# Schematic_L0.net
KiCad netlist of a schematic drawn in Altium Designer
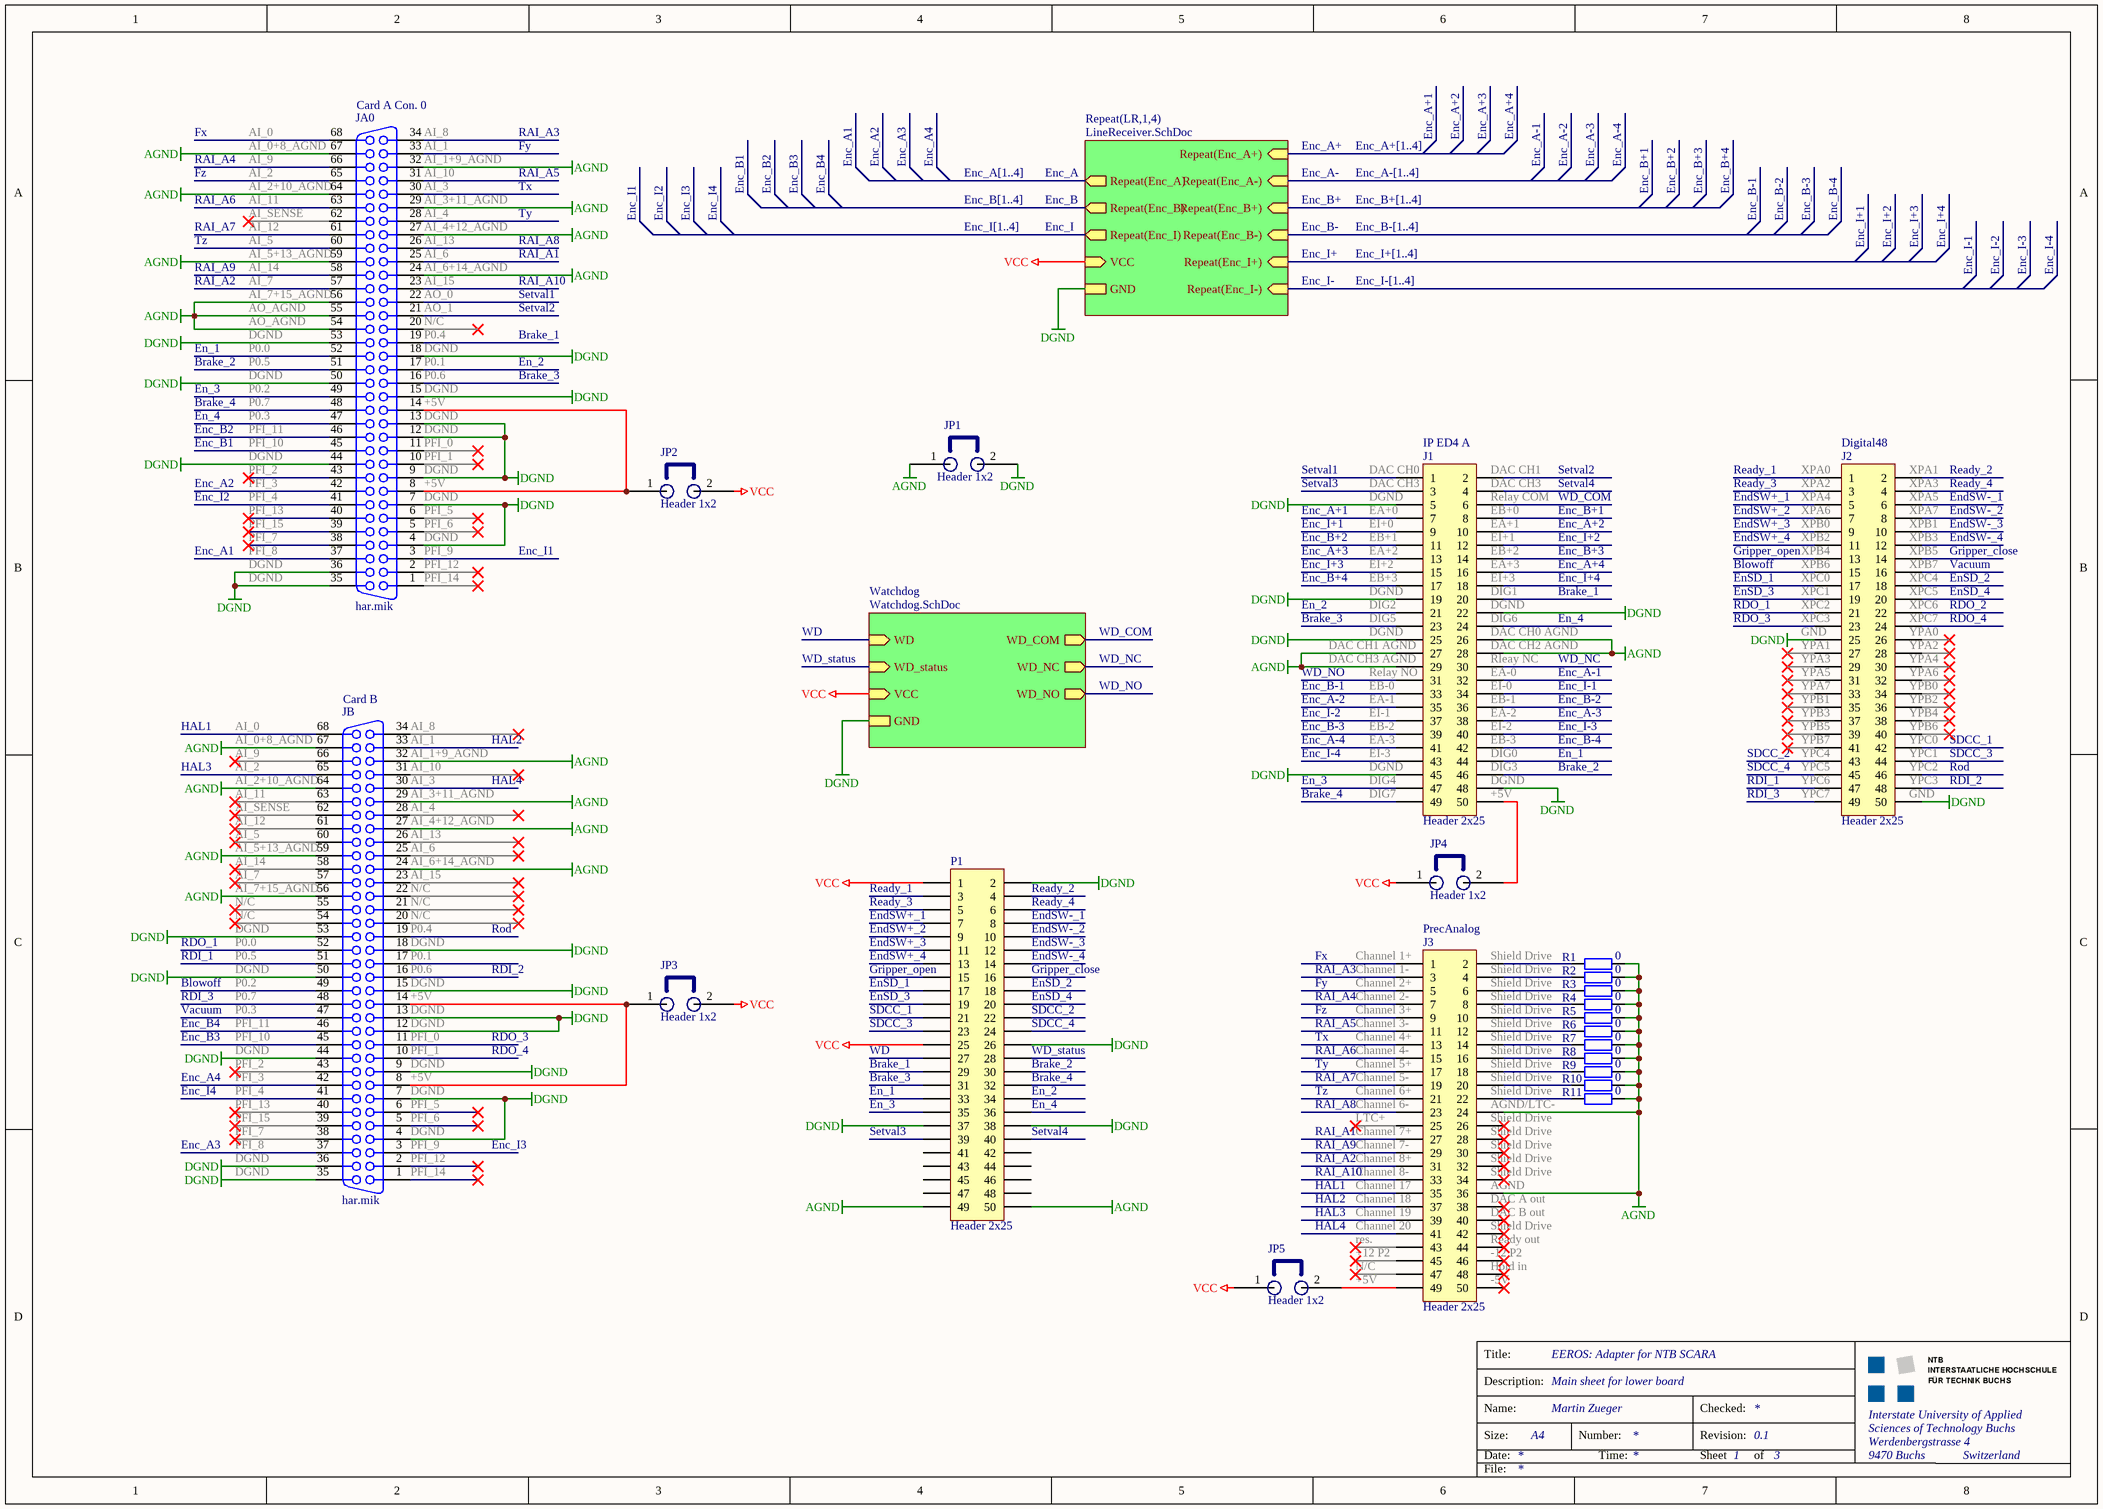
[diagram p0: Schematic_L0.SchDoc]

(export (version "E")
  (design (tool "Eeschema 10.0.6"))
  (components
    (comp (ref "J1")
      (value "Header 2x25")
      (footprint "Header - 2x25 - Boxed")
      (description "Header, 25-Pin, Dual row")
      (fields (field (name "PUBLISHER") "Altium Limited"))
      (libsource (lib "Integrated_Library") (part "Header 2x25"))
    )
    (comp (ref "J2")
      (value "Header 2x25")
      (footprint "Header - 2x25 - Boxed")
      (description "Header, 25-Pin, Dual row")
      (fields (field (name "PUBLISHER") "Altium Limited"))
      (libsource (lib "Integrated_Library") (part "Header 2x25"))
    )
    (comp (ref "J3")
      (value "Header 2x25")
      (footprint "Header - 2x25 - Boxed")
      (description "Header, 25-Pin, Dual row")
      (fields (field (name "PUBLISHER") "Altium Limited"))
      (libsource (lib "Integrated_Library") (part "Header 2x25"))
    )
    (comp (ref "JA0")
      (value "har.mik")
      (footprint "HAR-MIK P/S 68 SA")
      (description "TB 60 01 068 5232")
      (fields (field (name "PUBLISHER") "Altium Limited"))
      (libsource (lib "Integrated_Library") (part "Connector 68"))
    )
    (comp (ref "JB")
      (value "har.mik")
      (footprint "HAR-MIK P/S 68 SA")
      (description "TB 60 01 068 5232")
      (fields (field (name "PUBLISHER") "Altium Limited"))
      (libsource (lib "Integrated_Library") (part "Connector 68"))
    )
    (comp (ref "JP1")
      (value "Header 1x2")
      (footprint "Header - 1x2 - V")
      (libsource (lib "Integrated_Library") (part "Jumper"))
    )
    (comp (ref "JP2")
      (value "Header 1x2")
      (footprint "Header - 1x2 - V")
      (libsource (lib "Integrated_Library") (part "Jumper"))
    )
    (comp (ref "JP3")
      (value "Header 1x2")
      (footprint "Header - 1x2 - V")
      (libsource (lib "Integrated_Library") (part "Jumper"))
    )
    (comp (ref "JP4")
      (value "Header 1x2")
      (footprint "Header - 1x2 - V")
      (libsource (lib "Integrated_Library") (part "Jumper"))
    )
    (comp (ref "JP5")
      (value "Header 1x2")
      (footprint "Header - 1x2 - V")
      (libsource (lib "Integrated_Library") (part "Jumper"))
    )
    (comp (ref "P1")
      (value "Header 2x25")
      (footprint "Header - 2x25 - V")
      (description "Header, 25-Pin, Dual row")
      (fields (field (name "PUBLISHER") "Altium Limited"))
      (libsource (lib "mzueger") (part "Header 2x25"))
    )
    (comp (ref "R1")
      (value "0")
      (footprint "0805")
      (description "Resistor")
      (fields (field (name "#PUBLISHER") "Dr. A. Heinzelmann"))
      (libsource (lib "mzueger") (part "R"))
    )
    (comp (ref "R2")
      (value "0")
      (footprint "0805")
      (description "Resistor")
      (fields (field (name "#PUBLISHER") "Dr. A. Heinzelmann"))
      (libsource (lib "mzueger") (part "R"))
    )
    (comp (ref "R3")
      (value "0")
      (footprint "0805")
      (description "Resistor")
      (fields (field (name "#PUBLISHER") "Dr. A. Heinzelmann"))
      (libsource (lib "mzueger") (part "R"))
    )
    (comp (ref "R4")
      (value "0")
      (footprint "0805")
      (description "Resistor")
      (fields (field (name "#PUBLISHER") "Dr. A. Heinzelmann"))
      (libsource (lib "mzueger") (part "R"))
    )
    (comp (ref "R5")
      (value "0")
      (footprint "0805")
      (description "Resistor")
      (fields (field (name "#PUBLISHER") "Dr. A. Heinzelmann"))
      (libsource (lib "mzueger") (part "R"))
    )
    (comp (ref "R6")
      (value "0")
      (footprint "0805")
      (description "Resistor")
      (fields (field (name "#PUBLISHER") "Dr. A. Heinzelmann"))
      (libsource (lib "mzueger") (part "R"))
    )
    (comp (ref "R7")
      (value "0")
      (footprint "0805")
      (description "Resistor")
      (fields (field (name "#PUBLISHER") "Dr. A. Heinzelmann"))
      (libsource (lib "mzueger") (part "R"))
    )
    (comp (ref "R8")
      (value "0")
      (footprint "0805")
      (description "Resistor")
      (fields (field (name "#PUBLISHER") "Dr. A. Heinzelmann"))
      (libsource (lib "mzueger") (part "R"))
    )
    (comp (ref "R9")
      (value "0")
      (footprint "0805")
      (description "Resistor")
      (fields (field (name "#PUBLISHER") "Dr. A. Heinzelmann"))
      (libsource (lib "mzueger") (part "R"))
    )
    (comp (ref "R10")
      (value "0")
      (footprint "0805")
      (description "Resistor")
      (fields (field (name "#PUBLISHER") "Dr. A. Heinzelmann"))
      (libsource (lib "mzueger") (part "R"))
    )
    (comp (ref "R11")
      (value "0")
      (footprint "0805")
      (description "Resistor")
      (fields (field (name "#PUBLISHER") "Dr. A. Heinzelmann"))
      (libsource (lib "mzueger") (part "R"))
    )
  )
  (nets
    (net (code "1") (name "/Blowoff") (class "Default")
      (node (ref "J2") (pin "15") (pinfunction "15_15") (pintype "passive"))
      (node (ref "JB") (pin "49") (pinfunction "49_49") (pintype "passive"))
    )
    (net (code "2") (name "/Brake_1") (class "Default")
      (node (ref "J1") (pin "20") (pinfunction "20_20") (pintype "passive"))
      (node (ref "JA0") (pin "19") (pinfunction "19_19") (pintype "passive"))
      (node (ref "P1") (pin "29") (pinfunction "29_29") (pintype "passive"))
    )
    (net (code "3") (name "/Brake_2") (class "Default")
      (node (ref "J1") (pin "46") (pinfunction "46_46") (pintype "passive"))
      (node (ref "JA0") (pin "51") (pinfunction "51_51") (pintype "passive"))
      (node (ref "P1") (pin "30") (pinfunction "30_30") (pintype "passive"))
    )
    (net (code "4") (name "/Brake_3") (class "Default")
      (node (ref "J1") (pin "23") (pinfunction "23_23") (pintype "passive"))
      (node (ref "JA0") (pin "16") (pinfunction "16_16") (pintype "passive"))
      (node (ref "P1") (pin "31") (pinfunction "31_31") (pintype "passive"))
    )
    (net (code "5") (name "/Brake_4") (class "Default")
      (node (ref "J1") (pin "49") (pinfunction "49_49") (pintype "passive"))
      (node (ref "JA0") (pin "48") (pinfunction "48_48") (pintype "passive"))
      (node (ref "P1") (pin "32") (pinfunction "32_32") (pintype "passive"))
    )
    (net (code "6") (name "/EnSD_1") (class "Default")
      (node (ref "J2") (pin "17") (pinfunction "17_17") (pintype "passive"))
      (node (ref "P1") (pin "17") (pinfunction "17_17") (pintype "passive"))
    )
    (net (code "7") (name "/EnSD_2") (class "Default")
      (node (ref "J2") (pin "18") (pinfunction "18_18") (pintype "passive"))
      (node (ref "P1") (pin "18") (pinfunction "18_18") (pintype "passive"))
    )
    (net (code "8") (name "/EnSD_3") (class "Default")
      (node (ref "J2") (pin "19") (pinfunction "19_19") (pintype "passive"))
      (node (ref "P1") (pin "19") (pinfunction "19_19") (pintype "passive"))
    )
    (net (code "9") (name "/EnSD_4") (class "Default")
      (node (ref "J2") (pin "20") (pinfunction "20_20") (pintype "passive"))
      (node (ref "P1") (pin "20") (pinfunction "20_20") (pintype "passive"))
    )
    (net (code "10") (name "/En_1") (class "Default")
      (node (ref "J1") (pin "44") (pinfunction "44_44") (pintype "passive"))
      (node (ref "JA0") (pin "52") (pinfunction "52_52") (pintype "passive"))
      (node (ref "P1") (pin "33") (pinfunction "33_33") (pintype "passive"))
    )
    (net (code "11") (name "/En_2") (class "Default")
      (node (ref "J1") (pin "21") (pinfunction "21_21") (pintype "passive"))
      (node (ref "JA0") (pin "17") (pinfunction "17_17") (pintype "passive"))
      (node (ref "P1") (pin "34") (pinfunction "34_34") (pintype "passive"))
    )
    (net (code "12") (name "/En_3") (class "Default")
      (node (ref "J1") (pin "47") (pinfunction "47_47") (pintype "passive"))
      (node (ref "JA0") (pin "49") (pinfunction "49_49") (pintype "passive"))
      (node (ref "P1") (pin "35") (pinfunction "35_35") (pintype "passive"))
    )
    (net (code "13") (name "/En_4") (class "Default")
      (node (ref "J1") (pin "24") (pinfunction "24_24") (pintype "passive"))
      (node (ref "JA0") (pin "47") (pinfunction "47_47") (pintype "passive"))
      (node (ref "P1") (pin "36") (pinfunction "36_36") (pintype "passive"))
    )
    (net (code "16") (name "/Enc_A+1") (class "Default")
      (node (ref "J1") (pin "7") (pinfunction "7_7") (pintype "passive"))
    )
    (net (code "17") (name "/Enc_A+2") (class "Default")
      (node (ref "J1") (pin "10") (pinfunction "10_10") (pintype "passive"))
    )
    (net (code "18") (name "/Enc_A+3") (class "Default")
      (node (ref "J1") (pin "13") (pinfunction "13_13") (pintype "passive"))
    )
    (net (code "19") (name "/Enc_A+4") (class "Default")
      (node (ref "J1") (pin "16") (pinfunction "16_16") (pintype "passive"))
    )
    (net (code "22") (name "/Enc_A-1") (class "Default")
      (node (ref "J1") (pin "32") (pinfunction "32_32") (pintype "passive"))
    )
    (net (code "23") (name "/Enc_A-2") (class "Default")
      (node (ref "J1") (pin "35") (pinfunction "35_35") (pintype "passive"))
    )
    (net (code "24") (name "/Enc_A-3") (class "Default")
      (node (ref "J1") (pin "38") (pinfunction "38_38") (pintype "passive"))
    )
    (net (code "25") (name "/Enc_A-4") (class "Default")
      (node (ref "J1") (pin "41") (pinfunction "41_41") (pintype "passive"))
    )
    (net (code "27") (name "/Enc_A1") (class "Default")
      (node (ref "JA0") (pin "37") (pinfunction "37_37") (pintype "passive"))
    )
    (net (code "28") (name "/Enc_A2") (class "Default")
      (node (ref "JA0") (pin "42") (pinfunction "42_42") (pintype "passive"))
    )
    (net (code "29") (name "/Enc_A3") (class "Default")
      (node (ref "JB") (pin "37") (pinfunction "37_37") (pintype "passive"))
    )
    (net (code "30") (name "/Enc_A4") (class "Default")
      (node (ref "JB") (pin "42") (pinfunction "42_42") (pintype "passive"))
    )
    (net (code "34") (name "/Enc_B+1") (class "Default")
      (node (ref "J1") (pin "8") (pinfunction "8_8") (pintype "passive"))
    )
    (net (code "35") (name "/Enc_B+2") (class "Default")
      (node (ref "J1") (pin "11") (pinfunction "11_11") (pintype "passive"))
    )
    (net (code "36") (name "/Enc_B+3") (class "Default")
      (node (ref "J1") (pin "14") (pinfunction "14_14") (pintype "passive"))
    )
    (net (code "37") (name "/Enc_B+4") (class "Default")
      (node (ref "J1") (pin "17") (pinfunction "17_17") (pintype "passive"))
    )
    (net (code "40") (name "/Enc_B-1") (class "Default")
      (node (ref "J1") (pin "33") (pinfunction "33_33") (pintype "passive"))
    )
    (net (code "41") (name "/Enc_B-2") (class "Default")
      (node (ref "J1") (pin "36") (pinfunction "36_36") (pintype "passive"))
    )
    (net (code "42") (name "/Enc_B-3") (class "Default")
      (node (ref "J1") (pin "39") (pinfunction "39_39") (pintype "passive"))
    )
    (net (code "43") (name "/Enc_B-4") (class "Default")
      (node (ref "J1") (pin "42") (pinfunction "42_42") (pintype "passive"))
    )
    (net (code "45") (name "/Enc_B1") (class "Default")
      (node (ref "JA0") (pin "45") (pinfunction "45_45") (pintype "passive"))
    )
    (net (code "46") (name "/Enc_B2") (class "Default")
      (node (ref "JA0") (pin "46") (pinfunction "46_46") (pintype "passive"))
    )
    (net (code "47") (name "/Enc_B3") (class "Default")
      (node (ref "JB") (pin "45") (pinfunction "45_45") (pintype "passive"))
    )
    (net (code "48") (name "/Enc_B4") (class "Default")
      (node (ref "JB") (pin "46") (pinfunction "46_46") (pintype "passive"))
    )
    (net (code "52") (name "/Enc_I+1") (class "Default")
      (node (ref "J1") (pin "9") (pinfunction "9_9") (pintype "passive"))
    )
    (net (code "53") (name "/Enc_I+2") (class "Default")
      (node (ref "J1") (pin "12") (pinfunction "12_12") (pintype "passive"))
    )
    (net (code "54") (name "/Enc_I+3") (class "Default")
      (node (ref "J1") (pin "15") (pinfunction "15_15") (pintype "passive"))
    )
    (net (code "55") (name "/Enc_I+4") (class "Default")
      (node (ref "J1") (pin "18") (pinfunction "18_18") (pintype "passive"))
    )
    (net (code "58") (name "/Enc_I-1") (class "Default")
      (node (ref "J1") (pin "34") (pinfunction "34_34") (pintype "passive"))
    )
    (net (code "59") (name "/Enc_I-2") (class "Default")
      (node (ref "J1") (pin "37") (pinfunction "37_37") (pintype "passive"))
    )
    (net (code "60") (name "/Enc_I-3") (class "Default")
      (node (ref "J1") (pin "40") (pinfunction "40_40") (pintype "passive"))
    )
    (net (code "61") (name "/Enc_I-4") (class "Default")
      (node (ref "J1") (pin "43") (pinfunction "43_43") (pintype "passive"))
    )
    (net (code "63") (name "/Enc_I1") (class "Default")
      (node (ref "JA0") (pin "3") (pinfunction "3_3") (pintype "passive"))
    )
    (net (code "64") (name "/Enc_I2") (class "Default")
      (node (ref "JA0") (pin "41") (pinfunction "41_41") (pintype "passive"))
    )
    (net (code "65") (name "/Enc_I3") (class "Default")
      (node (ref "JB") (pin "3") (pinfunction "3_3") (pintype "passive"))
    )
    (net (code "66") (name "/Enc_I4") (class "Default")
      (node (ref "JB") (pin "41") (pinfunction "41_41") (pintype "passive"))
    )
    (net (code "68") (name "/EndSW+_1") (class "Default")
      (node (ref "J2") (pin "5") (pinfunction "5_5") (pintype "passive"))
      (node (ref "P1") (pin "7") (pinfunction "7_7") (pintype "passive"))
    )
    (net (code "69") (name "/EndSW+_2") (class "Default")
      (node (ref "J2") (pin "7") (pinfunction "7_7") (pintype "passive"))
      (node (ref "P1") (pin "9") (pinfunction "9_9") (pintype "passive"))
    )
    (net (code "70") (name "/EndSW+_3") (class "Default")
      (node (ref "J2") (pin "9") (pinfunction "9_9") (pintype "passive"))
      (node (ref "P1") (pin "11") (pinfunction "11_11") (pintype "passive"))
    )
    (net (code "71") (name "/EndSW+_4") (class "Default")
      (node (ref "J2") (pin "11") (pinfunction "11_11") (pintype "passive"))
      (node (ref "P1") (pin "13") (pinfunction "13_13") (pintype "passive"))
    )
    (net (code "72") (name "/EndSW-_1") (class "Default")
      (node (ref "J2") (pin "6") (pinfunction "6_6") (pintype "passive"))
      (node (ref "P1") (pin "8") (pinfunction "8_8") (pintype "passive"))
    )
    (net (code "73") (name "/EndSW-_2") (class "Default")
      (node (ref "J2") (pin "8") (pinfunction "8_8") (pintype "passive"))
      (node (ref "P1") (pin "10") (pinfunction "10_10") (pintype "passive"))
    )
    (net (code "74") (name "/EndSW-_3") (class "Default")
      (node (ref "J2") (pin "10") (pinfunction "10_10") (pintype "passive"))
      (node (ref "P1") (pin "12") (pinfunction "12_12") (pintype "passive"))
    )
    (net (code "75") (name "/EndSW-_4") (class "Default")
      (node (ref "J2") (pin "12") (pinfunction "12_12") (pintype "passive"))
      (node (ref "P1") (pin "14") (pinfunction "14_14") (pintype "passive"))
    )
    (net (code "76") (name "/Fx") (class "Default")
      (node (ref "J3") (pin "1") (pinfunction "1_1") (pintype "passive"))
      (node (ref "JA0") (pin "68") (pinfunction "68_68") (pintype "passive"))
    )
    (net (code "77") (name "/Fy") (class "Default")
      (node (ref "J3") (pin "5") (pinfunction "5_5") (pintype "passive"))
      (node (ref "JA0") (pin "33") (pinfunction "33_33") (pintype "passive"))
    )
    (net (code "78") (name "/Fz") (class "Default")
      (node (ref "J3") (pin "9") (pinfunction "9_9") (pintype "passive"))
      (node (ref "JA0") (pin "65") (pinfunction "65_65") (pintype "passive"))
    )
    (net (code "79") (name "/Gripper_close") (class "Default")
      (node (ref "J2") (pin "14") (pinfunction "14_14") (pintype "passive"))
      (node (ref "P1") (pin "16") (pinfunction "16_16") (pintype "passive"))
    )
    (net (code "80") (name "/Gripper_open") (class "Default")
      (node (ref "J2") (pin "13") (pinfunction "13_13") (pintype "passive"))
      (node (ref "P1") (pin "15") (pinfunction "15_15") (pintype "passive"))
    )
    (net (code "81") (name "/HAL1") (class "Default")
      (node (ref "J3") (pin "35") (pinfunction "35_35") (pintype "passive"))
      (node (ref "JB") (pin "68") (pinfunction "68_68") (pintype "passive"))
    )
    (net (code "82") (name "/HAL2") (class "Default")
      (node (ref "J3") (pin "37") (pinfunction "37_37") (pintype "passive"))
      (node (ref "JB") (pin "33") (pinfunction "33_33") (pintype "passive"))
    )
    (net (code "83") (name "/HAL3") (class "Default")
      (node (ref "J3") (pin "39") (pinfunction "39_39") (pintype "passive"))
      (node (ref "JB") (pin "65") (pinfunction "65_65") (pintype "passive"))
    )
    (net (code "84") (name "/HAL4") (class "Default")
      (node (ref "J3") (pin "41") (pinfunction "41_41") (pintype "passive"))
      (node (ref "JB") (pin "30") (pinfunction "30_30") (pintype "passive"))
    )
    (net (code "85") (name "/RAI_A1") (class "Default")
      (node (ref "J3") (pin "27") (pinfunction "27_27") (pintype "passive"))
      (node (ref "JA0") (pin "25") (pinfunction "25_25") (pintype "passive"))
    )
    (net (code "86") (name "/RAI_A2") (class "Default")
      (node (ref "J3") (pin "31") (pinfunction "31_31") (pintype "passive"))
      (node (ref "JA0") (pin "57") (pinfunction "57_57") (pintype "passive"))
    )
    (net (code "87") (name "/RAI_A3") (class "Default")
      (node (ref "J3") (pin "3") (pinfunction "3_3") (pintype "passive"))
      (node (ref "JA0") (pin "34") (pinfunction "34_34") (pintype "passive"))
    )
    (net (code "88") (name "/RAI_A4") (class "Default")
      (node (ref "J3") (pin "7") (pinfunction "7_7") (pintype "passive"))
      (node (ref "JA0") (pin "66") (pinfunction "66_66") (pintype "passive"))
    )
    (net (code "89") (name "/RAI_A5") (class "Default")
      (node (ref "J3") (pin "11") (pinfunction "11_11") (pintype "passive"))
      (node (ref "JA0") (pin "31") (pinfunction "31_31") (pintype "passive"))
    )
    (net (code "90") (name "/RAI_A6") (class "Default")
      (node (ref "J3") (pin "15") (pinfunction "15_15") (pintype "passive"))
      (node (ref "JA0") (pin "63") (pinfunction "63_63") (pintype "passive"))
    )
    (net (code "91") (name "/RAI_A7") (class "Default")
      (node (ref "J3") (pin "19") (pinfunction "19_19") (pintype "passive"))
      (node (ref "JA0") (pin "61") (pinfunction "61_61") (pintype "passive"))
    )
    (net (code "92") (name "/RAI_A8") (class "Default")
      (node (ref "J3") (pin "23") (pinfunction "23_23") (pintype "passive"))
      (node (ref "JA0") (pin "26") (pinfunction "26_26") (pintype "passive"))
    )
    (net (code "93") (name "/RAI_A9") (class "Default")
      (node (ref "J3") (pin "29") (pinfunction "29_29") (pintype "passive"))
      (node (ref "JA0") (pin "58") (pinfunction "58_58") (pintype "passive"))
    )
    (net (code "94") (name "/RAI_A10") (class "Default")
      (node (ref "J3") (pin "33") (pinfunction "33_33") (pintype "passive"))
      (node (ref "JA0") (pin "23") (pinfunction "23_23") (pintype "passive"))
    )
    (net (code "95") (name "/RDI_1") (class "Default")
      (node (ref "J2") (pin "47") (pinfunction "47_47") (pintype "passive"))
      (node (ref "JB") (pin "51") (pinfunction "51_51") (pintype "passive"))
    )
    (net (code "96") (name "/RDI_2") (class "Default")
      (node (ref "J2") (pin "48") (pinfunction "48_48") (pintype "passive"))
      (node (ref "JB") (pin "16") (pinfunction "16_16") (pintype "passive"))
    )
    (net (code "97") (name "/RDI_3") (class "Default")
      (node (ref "J2") (pin "49") (pinfunction "49_49") (pintype "passive"))
      (node (ref "JB") (pin "48") (pinfunction "48_48") (pintype "passive"))
    )
    (net (code "98") (name "/RDO_1") (class "Default")
      (node (ref "J2") (pin "21") (pinfunction "21_21") (pintype "passive"))
      (node (ref "JB") (pin "52") (pinfunction "52_52") (pintype "passive"))
    )
    (net (code "99") (name "/RDO_2") (class "Default")
      (node (ref "J2") (pin "22") (pinfunction "22_22") (pintype "passive"))
    )
    (net (code "100") (name "/RDO_3") (class "Default")
      (node (ref "J2") (pin "23") (pinfunction "23_23") (pintype "passive"))
      (node (ref "JB") (pin "11") (pinfunction "11_11") (pintype "passive"))
    )
    (net (code "101") (name "/RDO_4") (class "Default")
      (node (ref "J2") (pin "24") (pinfunction "24_24") (pintype "passive"))
      (node (ref "JB") (pin "10") (pinfunction "10_10") (pintype "passive"))
    )
    (net (code "102") (name "/Ready_1") (class "Default")
      (node (ref "J2") (pin "1") (pinfunction "1_1") (pintype "passive"))
      (node (ref "P1") (pin "3") (pinfunction "3_3") (pintype "passive"))
    )
    (net (code "103") (name "/Ready_2") (class "Default")
      (node (ref "J2") (pin "2") (pinfunction "2_2") (pintype "passive"))
      (node (ref "P1") (pin "4") (pinfunction "4_4") (pintype "passive"))
    )
    (net (code "104") (name "/Ready_3") (class "Default")
      (node (ref "J2") (pin "3") (pinfunction "3_3") (pintype "passive"))
      (node (ref "P1") (pin "5") (pinfunction "5_5") (pintype "passive"))
    )
    (net (code "105") (name "/Ready_4") (class "Default")
      (node (ref "J2") (pin "4") (pinfunction "4_4") (pintype "passive"))
      (node (ref "P1") (pin "6") (pinfunction "6_6") (pintype "passive"))
    )
    (net (code "106") (name "/Rod") (class "Default")
      (node (ref "J2") (pin "46") (pinfunction "46_46") (pintype "passive"))
      (node (ref "JB") (pin "19") (pinfunction "19_19") (pintype "passive"))
    )
    (net (code "107") (name "/SDCC_1") (class "Default")
      (node (ref "J2") (pin "42") (pinfunction "42_42") (pintype "passive"))
      (node (ref "P1") (pin "21") (pinfunction "21_21") (pintype "passive"))
    )
    (net (code "108") (name "/SDCC_2") (class "Default")
      (node (ref "J2") (pin "43") (pinfunction "43_43") (pintype "passive"))
      (node (ref "P1") (pin "22") (pinfunction "22_22") (pintype "passive"))
    )
    (net (code "109") (name "/SDCC_3") (class "Default")
      (node (ref "J2") (pin "44") (pinfunction "44_44") (pintype "passive"))
      (node (ref "P1") (pin "23") (pinfunction "23_23") (pintype "passive"))
    )
    (net (code "110") (name "/SDCC_4") (class "Default")
      (node (ref "J2") (pin "45") (pinfunction "45_45") (pintype "passive"))
      (node (ref "P1") (pin "24") (pinfunction "24_24") (pintype "passive"))
    )
    (net (code "111") (name "/Setval1") (class "Default")
      (node (ref "J1") (pin "1") (pinfunction "1_1") (pintype "passive"))
      (node (ref "JA0") (pin "22") (pinfunction "22_22") (pintype "passive"))
    )
    (net (code "112") (name "/Setval2") (class "Default")
      (node (ref "J1") (pin "2") (pinfunction "2_2") (pintype "passive"))
      (node (ref "JA0") (pin "21") (pinfunction "21_21") (pintype "passive"))
    )
    (net (code "113") (name "/Setval3") (class "Default")
      (node (ref "J1") (pin "3") (pinfunction "3_3") (pintype "passive"))
      (node (ref "P1") (pin "39") (pinfunction "39_39") (pintype "passive"))
    )
    (net (code "114") (name "/Setval4") (class "Default")
      (node (ref "J1") (pin "4") (pinfunction "4_4") (pintype "passive"))
      (node (ref "P1") (pin "40") (pinfunction "40_40") (pintype "passive"))
    )
    (net (code "115") (name "/Tx") (class "Default")
      (node (ref "J3") (pin "13") (pinfunction "13_13") (pintype "passive"))
      (node (ref "JA0") (pin "30") (pinfunction "30_30") (pintype "passive"))
    )
    (net (code "116") (name "/Ty") (class "Default")
      (node (ref "J3") (pin "17") (pinfunction "17_17") (pintype "passive"))
      (node (ref "JA0") (pin "28") (pinfunction "28_28") (pintype "passive"))
    )
    (net (code "117") (name "/Tz") (class "Default")
      (node (ref "J3") (pin "21") (pinfunction "21_21") (pintype "passive"))
      (node (ref "JA0") (pin "60") (pinfunction "60_60") (pintype "passive"))
    )
    (net (code "118") (name "/Vacuum") (class "Default")
      (node (ref "J2") (pin "16") (pinfunction "16_16") (pintype "passive"))
      (node (ref "JB") (pin "47") (pinfunction "47_47") (pintype "passive"))
    )
    (net (code "119") (name "/WD") (class "Default")
      (node (ref "P1") (pin "27") (pinfunction "27_27") (pintype "passive"))
    )
    (net (code "120") (name "/WD_COM") (class "Default")
      (node (ref "J1") (pin "6") (pinfunction "6_6") (pintype "passive"))
    )
    (net (code "121") (name "/WD_NC") (class "Default")
      (node (ref "J1") (pin "30") (pinfunction "30_30") (pintype "passive"))
    )
    (net (code "122") (name "/WD_NO") (class "Default")
      (node (ref "J1") (pin "31") (pinfunction "31_31") (pintype "passive"))
    )
    (net (code "123") (name "/WD_status") (class "Default")
      (node (ref "P1") (pin "28") (pinfunction "28_28") (pintype "passive"))
    )
    (net (code "124") (name "AGND") (class "Default")
      (node (ref "J1") (pin "26") (pinfunction "26_26") (pintype "passive"))
      (node (ref "J1") (pin "27") (pinfunction "27_27") (pintype "passive"))
      (node (ref "J1") (pin "28") (pinfunction "28_28") (pintype "passive"))
      (node (ref "J1") (pin "29") (pinfunction "29_29") (pintype "passive"))
      (node (ref "J3") (pin "24") (pinfunction "24_24") (pintype "passive"))
      (node (ref "J3") (pin "36") (pinfunction "36_36") (pintype "passive"))
      (node (ref "JA0") (pin "24") (pinfunction "24_24") (pintype "passive"))
      (node (ref "JA0") (pin "27") (pinfunction "27_27") (pintype "passive"))
      (node (ref "JA0") (pin "29") (pinfunction "29_29") (pintype "passive"))
      (node (ref "JA0") (pin "32") (pinfunction "32_32") (pintype "passive"))
      (node (ref "JA0") (pin "54") (pinfunction "54_54") (pintype "passive"))
      (node (ref "JA0") (pin "55") (pinfunction "55_55") (pintype "passive"))
      (node (ref "JA0") (pin "56") (pinfunction "56_56") (pintype "passive"))
      (node (ref "JA0") (pin "59") (pinfunction "59_59") (pintype "passive"))
      (node (ref "JA0") (pin "64") (pinfunction "64_64") (pintype "passive"))
      (node (ref "JA0") (pin "67") (pinfunction "67_67") (pintype "passive"))
      (node (ref "JB") (pin "24") (pinfunction "24_24") (pintype "passive"))
      (node (ref "JB") (pin "27") (pinfunction "27_27") (pintype "passive"))
      (node (ref "JB") (pin "29") (pinfunction "29_29") (pintype "passive"))
      (node (ref "JB") (pin "32") (pinfunction "32_32") (pintype "passive"))
      (node (ref "JB") (pin "56") (pinfunction "56_56") (pintype "passive"))
      (node (ref "JB") (pin "59") (pinfunction "59_59") (pintype "passive"))
      (node (ref "JB") (pin "64") (pinfunction "64_64") (pintype "passive"))
      (node (ref "JB") (pin "67") (pinfunction "67_67") (pintype "passive"))
      (node (ref "JP1") (pin "1") (pinfunction "1_1") (pintype "passive"))
      (node (ref "P1") (pin "49") (pinfunction "49_49") (pintype "passive"))
      (node (ref "P1") (pin "50") (pinfunction "50_50") (pintype "passive"))
      (node (ref "R1") (pin "2") (pinfunction "2_2") (pintype "passive"))
      (node (ref "R10") (pin "2") (pinfunction "2_2") (pintype "passive"))
      (node (ref "R11") (pin "2") (pinfunction "2_2") (pintype "passive"))
      (node (ref "R2") (pin "2") (pinfunction "2_2") (pintype "passive"))
      (node (ref "R3") (pin "2") (pinfunction "2_2") (pintype "passive"))
      (node (ref "R4") (pin "2") (pinfunction "2_2") (pintype "passive"))
      (node (ref "R5") (pin "2") (pinfunction "2_2") (pintype "passive"))
      (node (ref "R6") (pin "2") (pinfunction "2_2") (pintype "passive"))
      (node (ref "R7") (pin "2") (pinfunction "2_2") (pintype "passive"))
      (node (ref "R8") (pin "2") (pinfunction "2_2") (pintype "passive"))
      (node (ref "R9") (pin "2") (pinfunction "2_2") (pintype "passive"))
    )
    (net (code "125") (name "DGND") (class "Default")
      (node (ref "J1") (pin "19") (pinfunction "19_19") (pintype "passive"))
      (node (ref "J1") (pin "22") (pinfunction "22_22") (pintype "passive"))
      (node (ref "J1") (pin "25") (pinfunction "25_25") (pintype "passive"))
      (node (ref "J1") (pin "45") (pinfunction "45_45") (pintype "passive"))
      (node (ref "J1") (pin "48") (pinfunction "48_48") (pintype "passive"))
      (node (ref "J1") (pin "5") (pinfunction "5_5") (pintype "passive"))
      (node (ref "J2") (pin "25") (pinfunction "25_25") (pintype "passive"))
      (node (ref "J2") (pin "50") (pinfunction "50_50") (pintype "passive"))
      (node (ref "JA0") (pin "12") (pinfunction "12_12") (pintype "passive"))
      (node (ref "JA0") (pin "13") (pinfunction "13_13") (pintype "passive"))
      (node (ref "JA0") (pin "15") (pinfunction "15_15") (pintype "passive"))
      (node (ref "JA0") (pin "18") (pinfunction "18_18") (pintype "passive"))
      (node (ref "JA0") (pin "35") (pinfunction "35_35") (pintype "passive"))
      (node (ref "JA0") (pin "36") (pinfunction "36_36") (pintype "passive"))
      (node (ref "JA0") (pin "4") (pinfunction "4_4") (pintype "passive"))
      (node (ref "JA0") (pin "44") (pinfunction "44_44") (pintype "passive"))
      (node (ref "JA0") (pin "50") (pinfunction "50_50") (pintype "passive"))
      (node (ref "JA0") (pin "53") (pinfunction "53_53") (pintype "passive"))
      (node (ref "JA0") (pin "7") (pinfunction "7_7") (pintype "passive"))
      (node (ref "JA0") (pin "9") (pinfunction "9_9") (pintype "passive"))
      (node (ref "JB") (pin "12") (pinfunction "12_12") (pintype "passive"))
      (node (ref "JB") (pin "13") (pinfunction "13_13") (pintype "passive"))
      (node (ref "JB") (pin "15") (pinfunction "15_15") (pintype "passive"))
      (node (ref "JB") (pin "18") (pinfunction "18_18") (pintype "passive"))
      (node (ref "JB") (pin "35") (pinfunction "35_35") (pintype "passive"))
      (node (ref "JB") (pin "36") (pinfunction "36_36") (pintype "passive"))
      (node (ref "JB") (pin "4") (pinfunction "4_4") (pintype "passive"))
      (node (ref "JB") (pin "44") (pinfunction "44_44") (pintype "passive"))
      (node (ref "JB") (pin "50") (pinfunction "50_50") (pintype "passive"))
      (node (ref "JB") (pin "53") (pinfunction "53_53") (pintype "passive"))
      (node (ref "JB") (pin "7") (pinfunction "7_7") (pintype "passive"))
      (node (ref "JB") (pin "9") (pinfunction "9_9") (pintype "passive"))
      (node (ref "JP1") (pin "2") (pinfunction "2_2") (pintype "passive"))
      (node (ref "P1") (pin "2") (pinfunction "2_2") (pintype "passive"))
      (node (ref "P1") (pin "26") (pinfunction "26_26") (pintype "passive"))
      (node (ref "P1") (pin "37") (pinfunction "37_37") (pintype "passive"))
      (node (ref "P1") (pin "38") (pinfunction "38_38") (pintype "passive"))
    )
    (net (code "126") (name "Net-(J1-Pad50)") (class "Default")
      (node (ref "J1") (pin "50") (pinfunction "50_50") (pintype "passive"))
      (node (ref "JP4") (pin "2") (pinfunction "2_2") (pintype "passive"))
    )
    (net (code "127") (name "Net-(J3-Pad2)") (class "Default")
      (node (ref "J3") (pin "2") (pinfunction "2_2") (pintype "passive"))
      (node (ref "R1") (pin "1") (pinfunction "1_1") (pintype "passive"))
    )
    (net (code "128") (name "Net-(J3-Pad4)") (class "Default")
      (node (ref "J3") (pin "4") (pinfunction "4_4") (pintype "passive"))
      (node (ref "R2") (pin "1") (pinfunction "1_1") (pintype "passive"))
    )
    (net (code "129") (name "Net-(J3-Pad6)") (class "Default")
      (node (ref "J3") (pin "6") (pinfunction "6_6") (pintype "passive"))
      (node (ref "R3") (pin "1") (pinfunction "1_1") (pintype "passive"))
    )
    (net (code "130") (name "Net-(J3-Pad8)") (class "Default")
      (node (ref "J3") (pin "8") (pinfunction "8_8") (pintype "passive"))
      (node (ref "R4") (pin "1") (pinfunction "1_1") (pintype "passive"))
    )
    (net (code "131") (name "Net-(J3-Pad10)") (class "Default")
      (node (ref "J3") (pin "10") (pinfunction "10_10") (pintype "passive"))
      (node (ref "R5") (pin "1") (pinfunction "1_1") (pintype "passive"))
    )
    (net (code "132") (name "Net-(J3-Pad12)") (class "Default")
      (node (ref "J3") (pin "12") (pinfunction "12_12") (pintype "passive"))
      (node (ref "R6") (pin "1") (pinfunction "1_1") (pintype "passive"))
    )
    (net (code "133") (name "Net-(J3-Pad14)") (class "Default")
      (node (ref "J3") (pin "14") (pinfunction "14_14") (pintype "passive"))
      (node (ref "R7") (pin "1") (pinfunction "1_1") (pintype "passive"))
    )
    (net (code "134") (name "Net-(J3-Pad16)") (class "Default")
      (node (ref "J3") (pin "16") (pinfunction "16_16") (pintype "passive"))
      (node (ref "R8") (pin "1") (pinfunction "1_1") (pintype "passive"))
    )
    (net (code "135") (name "Net-(J3-Pad18)") (class "Default")
      (node (ref "J3") (pin "18") (pinfunction "18_18") (pintype "passive"))
      (node (ref "R9") (pin "1") (pinfunction "1_1") (pintype "passive"))
    )
    (net (code "136") (name "Net-(J3-Pad20)") (class "Default")
      (node (ref "J3") (pin "20") (pinfunction "20_20") (pintype "passive"))
      (node (ref "R10") (pin "1") (pinfunction "1_1") (pintype "passive"))
    )
    (net (code "137") (name "Net-(J3-Pad22)") (class "Default")
      (node (ref "J3") (pin "22") (pinfunction "22_22") (pintype "passive"))
      (node (ref "R11") (pin "1") (pinfunction "1_1") (pintype "passive"))
    )
    (net (code "138") (name "Net-(J3-Pad49)") (class "Default")
      (node (ref "J3") (pin "49") (pinfunction "49_49") (pintype "passive"))
      (node (ref "JP5") (pin "2") (pinfunction "2_2") (pintype "passive"))
    )
    (net (code "139") (name "Net-(JA0-Pad14)") (class "Default")
      (node (ref "JA0") (pin "14") (pinfunction "14_14") (pintype "passive"))
      (node (ref "JA0") (pin "8") (pinfunction "8_8") (pintype "passive"))
      (node (ref "JP2") (pin "1") (pinfunction "1_1") (pintype "passive"))
    )
    (net (code "140") (name "Net-(JB-Pad14)") (class "Default")
      (node (ref "JB") (pin "14") (pinfunction "14_14") (pintype "passive"))
      (node (ref "JB") (pin "8") (pinfunction "8_8") (pintype "passive"))
      (node (ref "JP3") (pin "1") (pinfunction "1_1") (pintype "passive"))
    )
    (net (code "141") (name "VCC") (class "Default")
      (node (ref "JP2") (pin "2") (pinfunction "2_2") (pintype "passive"))
      (node (ref "JP3") (pin "2") (pinfunction "2_2") (pintype "passive"))
      (node (ref "JP4") (pin "1") (pinfunction "1_1") (pintype "passive"))
      (node (ref "JP5") (pin "1") (pinfunction "1_1") (pintype "passive"))
      (node (ref "P1") (pin "1") (pinfunction "1_1") (pintype "passive"))
      (node (ref "P1") (pin "25") (pinfunction "25_25") (pintype "passive"))
    )
    (net (code "142") (name "unconnected-(J2-Pad26)") (class "Default")
      (node (ref "J2") (pin "26") (pinfunction "26_26") (pintype "passive+no_connect"))
    )
    (net (code "143") (name "unconnected-(J2-Pad27)") (class "Default")
      (node (ref "J2") (pin "27") (pinfunction "27_27") (pintype "passive+no_connect"))
    )
    (net (code "144") (name "unconnected-(J2-Pad28)") (class "Default")
      (node (ref "J2") (pin "28") (pinfunction "28_28") (pintype "passive+no_connect"))
    )
    (net (code "145") (name "unconnected-(J2-Pad29)") (class "Default")
      (node (ref "J2") (pin "29") (pinfunction "29_29") (pintype "passive+no_connect"))
    )
    (net (code "146") (name "unconnected-(J2-Pad30)") (class "Default")
      (node (ref "J2") (pin "30") (pinfunction "30_30") (pintype "passive+no_connect"))
    )
    (net (code "147") (name "unconnected-(J2-Pad31)") (class "Default")
      (node (ref "J2") (pin "31") (pinfunction "31_31") (pintype "passive+no_connect"))
    )
    (net (code "148") (name "unconnected-(J2-Pad32)") (class "Default")
      (node (ref "J2") (pin "32") (pinfunction "32_32") (pintype "passive+no_connect"))
    )
    (net (code "149") (name "unconnected-(J2-Pad33)") (class "Default")
      (node (ref "J2") (pin "33") (pinfunction "33_33") (pintype "passive+no_connect"))
    )
    (net (code "150") (name "unconnected-(J2-Pad34)") (class "Default")
      (node (ref "J2") (pin "34") (pinfunction "34_34") (pintype "passive+no_connect"))
    )
    (net (code "151") (name "unconnected-(J2-Pad35)") (class "Default")
      (node (ref "J2") (pin "35") (pinfunction "35_35") (pintype "passive+no_connect"))
    )
    (net (code "152") (name "unconnected-(J2-Pad36)") (class "Default")
      (node (ref "J2") (pin "36") (pinfunction "36_36") (pintype "passive+no_connect"))
    )
    (net (code "153") (name "unconnected-(J2-Pad37)") (class "Default")
      (node (ref "J2") (pin "37") (pinfunction "37_37") (pintype "passive+no_connect"))
    )
    (net (code "154") (name "unconnected-(J2-Pad38)") (class "Default")
      (node (ref "J2") (pin "38") (pinfunction "38_38") (pintype "passive+no_connect"))
    )
    (net (code "155") (name "unconnected-(J2-Pad39)") (class "Default")
      (node (ref "J2") (pin "39") (pinfunction "39_39") (pintype "passive+no_connect"))
    )
    (net (code "156") (name "unconnected-(J2-Pad40)") (class "Default")
      (node (ref "J2") (pin "40") (pinfunction "40_40") (pintype "passive+no_connect"))
    )
    (net (code "157") (name "unconnected-(J2-Pad41)") (class "Default")
      (node (ref "J2") (pin "41") (pinfunction "41_41") (pintype "passive+no_connect"))
    )
    (net (code "158") (name "unconnected-(J3-Pad25)") (class "Default")
      (node (ref "J3") (pin "25") (pinfunction "25_25") (pintype "passive+no_connect"))
    )
    (net (code "159") (name "unconnected-(J3-Pad26)") (class "Default")
      (node (ref "J3") (pin "26") (pinfunction "26_26") (pintype "passive+no_connect"))
    )
    (net (code "160") (name "unconnected-(J3-Pad28)") (class "Default")
      (node (ref "J3") (pin "28") (pinfunction "28_28") (pintype "passive+no_connect"))
    )
    (net (code "161") (name "unconnected-(J3-Pad30)") (class "Default")
      (node (ref "J3") (pin "30") (pinfunction "30_30") (pintype "passive+no_connect"))
    )
    (net (code "162") (name "unconnected-(J3-Pad32)") (class "Default")
      (node (ref "J3") (pin "32") (pinfunction "32_32") (pintype "passive+no_connect"))
    )
    (net (code "163") (name "unconnected-(J3-Pad34)") (class "Default")
      (node (ref "J3") (pin "34") (pinfunction "34_34") (pintype "passive+no_connect"))
    )
    (net (code "164") (name "unconnected-(J3-Pad38)") (class "Default")
      (node (ref "J3") (pin "38") (pinfunction "38_38") (pintype "passive+no_connect"))
    )
    (net (code "165") (name "unconnected-(J3-Pad40)") (class "Default")
      (node (ref "J3") (pin "40") (pinfunction "40_40") (pintype "passive+no_connect"))
    )
    (net (code "166") (name "unconnected-(J3-Pad42)") (class "Default")
      (node (ref "J3") (pin "42") (pinfunction "42_42") (pintype "passive+no_connect"))
    )
    (net (code "167") (name "unconnected-(J3-Pad43)") (class "Default")
      (node (ref "J3") (pin "43") (pinfunction "43_43") (pintype "passive+no_connect"))
    )
    (net (code "168") (name "unconnected-(J3-Pad44)") (class "Default")
      (node (ref "J3") (pin "44") (pinfunction "44_44") (pintype "passive+no_connect"))
    )
    (net (code "169") (name "unconnected-(J3-Pad45)") (class "Default")
      (node (ref "J3") (pin "45") (pinfunction "45_45") (pintype "passive+no_connect"))
    )
    (net (code "170") (name "unconnected-(J3-Pad46)") (class "Default")
      (node (ref "J3") (pin "46") (pinfunction "46_46") (pintype "passive+no_connect"))
    )
    (net (code "171") (name "unconnected-(J3-Pad47)") (class "Default")
      (node (ref "J3") (pin "47") (pinfunction "47_47") (pintype "passive+no_connect"))
    )
    (net (code "172") (name "unconnected-(J3-Pad48)") (class "Default")
      (node (ref "J3") (pin "48") (pinfunction "48_48") (pintype "passive+no_connect"))
    )
    (net (code "173") (name "unconnected-(J3-Pad50)") (class "Default")
      (node (ref "J3") (pin "50") (pinfunction "50_50") (pintype "passive+no_connect"))
    )
    (net (code "174") (name "unconnected-(JA0-Pad1)") (class "Default")
      (node (ref "JA0") (pin "1") (pinfunction "1_1") (pintype "passive+no_connect"))
    )
    (net (code "175") (name "unconnected-(JA0-Pad2)") (class "Default")
      (node (ref "JA0") (pin "2") (pinfunction "2_2") (pintype "passive+no_connect"))
    )
    (net (code "176") (name "unconnected-(JA0-Pad5)") (class "Default")
      (node (ref "JA0") (pin "5") (pinfunction "5_5") (pintype "passive+no_connect"))
    )
    (net (code "177") (name "unconnected-(JA0-Pad6)") (class "Default")
      (node (ref "JA0") (pin "6") (pinfunction "6_6") (pintype "passive+no_connect"))
    )
    (net (code "178") (name "unconnected-(JA0-Pad10)") (class "Default")
      (node (ref "JA0") (pin "10") (pinfunction "10_10") (pintype "passive+no_connect"))
    )
    (net (code "179") (name "unconnected-(JA0-Pad11)") (class "Default")
      (node (ref "JA0") (pin "11") (pinfunction "11_11") (pintype "passive+no_connect"))
    )
    (net (code "180") (name "unconnected-(JA0-Pad20)") (class "Default")
      (node (ref "JA0") (pin "20") (pinfunction "20_20") (pintype "passive+no_connect"))
    )
    (net (code "181") (name "unconnected-(JA0-Pad38)") (class "Default")
      (node (ref "JA0") (pin "38") (pinfunction "38_38") (pintype "passive+no_connect"))
    )
    (net (code "182") (name "unconnected-(JA0-Pad39)") (class "Default")
      (node (ref "JA0") (pin "39") (pinfunction "39_39") (pintype "passive+no_connect"))
    )
    (net (code "183") (name "unconnected-(JA0-Pad40)") (class "Default")
      (node (ref "JA0") (pin "40") (pinfunction "40_40") (pintype "passive+no_connect"))
    )
    (net (code "184") (name "unconnected-(JA0-Pad43)") (class "Default")
      (node (ref "JA0") (pin "43") (pinfunction "43_43") (pintype "passive+no_connect"))
    )
    (net (code "185") (name "unconnected-(JA0-Pad62)") (class "Default")
      (node (ref "JA0") (pin "62") (pinfunction "62_62") (pintype "passive+no_connect"))
    )
    (net (code "186") (name "unconnected-(JB-Pad1)") (class "Default")
      (node (ref "JB") (pin "1") (pinfunction "1_1") (pintype "passive+no_connect"))
    )
    (net (code "187") (name "unconnected-(JB-Pad2)") (class "Default")
      (node (ref "JB") (pin "2") (pinfunction "2_2") (pintype "passive+no_connect"))
    )
    (net (code "188") (name "unconnected-(JB-Pad5)") (class "Default")
      (node (ref "JB") (pin "5") (pinfunction "5_5") (pintype "passive+no_connect"))
    )
    (net (code "189") (name "unconnected-(JB-Pad6)") (class "Default")
      (node (ref "JB") (pin "6") (pinfunction "6_6") (pintype "passive+no_connect"))
    )
    (net (code "190") (name "unconnected-(JB-Pad17)") (class "Default")
      (node (ref "JB") (pin "17") (pinfunction "17_17") (pintype "passive"))
    )
    (net (code "191") (name "unconnected-(JB-Pad20)") (class "Default")
      (node (ref "JB") (pin "20") (pinfunction "20_20") (pintype "passive+no_connect"))
    )
    (net (code "192") (name "unconnected-(JB-Pad21)") (class "Default")
      (node (ref "JB") (pin "21") (pinfunction "21_21") (pintype "passive+no_connect"))
    )
    (net (code "193") (name "unconnected-(JB-Pad22)") (class "Default")
      (node (ref "JB") (pin "22") (pinfunction "22_22") (pintype "passive+no_connect"))
    )
    (net (code "194") (name "unconnected-(JB-Pad23)") (class "Default")
      (node (ref "JB") (pin "23") (pinfunction "23_23") (pintype "passive+no_connect"))
    )
    (net (code "195") (name "unconnected-(JB-Pad25)") (class "Default")
      (node (ref "JB") (pin "25") (pinfunction "25_25") (pintype "passive+no_connect"))
    )
    (net (code "196") (name "unconnected-(JB-Pad26)") (class "Default")
      (node (ref "JB") (pin "26") (pinfunction "26_26") (pintype "passive+no_connect"))
    )
    (net (code "197") (name "unconnected-(JB-Pad28)") (class "Default")
      (node (ref "JB") (pin "28") (pinfunction "28_28") (pintype "passive+no_connect"))
    )
    (net (code "198") (name "unconnected-(JB-Pad31)") (class "Default")
      (node (ref "JB") (pin "31") (pinfunction "31_31") (pintype "passive+no_connect"))
    )
    (net (code "199") (name "unconnected-(JB-Pad34)") (class "Default")
      (node (ref "JB") (pin "34") (pinfunction "34_34") (pintype "passive+no_connect"))
    )
    (net (code "200") (name "unconnected-(JB-Pad38)") (class "Default")
      (node (ref "JB") (pin "38") (pinfunction "38_38") (pintype "passive+no_connect"))
    )
    (net (code "201") (name "unconnected-(JB-Pad39)") (class "Default")
      (node (ref "JB") (pin "39") (pinfunction "39_39") (pintype "passive+no_connect"))
    )
    (net (code "202") (name "unconnected-(JB-Pad40)") (class "Default")
      (node (ref "JB") (pin "40") (pinfunction "40_40") (pintype "passive+no_connect"))
    )
    (net (code "203") (name "unconnected-(JB-Pad43)") (class "Default")
      (node (ref "JB") (pin "43") (pinfunction "43_43") (pintype "passive+no_connect"))
    )
    (net (code "204") (name "unconnected-(JB-Pad54)") (class "Default")
      (node (ref "JB") (pin "54") (pinfunction "54_54") (pintype "passive+no_connect"))
    )
    (net (code "205") (name "unconnected-(JB-Pad55)") (class "Default")
      (node (ref "JB") (pin "55") (pinfunction "55_55") (pintype "passive+no_connect"))
    )
    (net (code "206") (name "unconnected-(JB-Pad57)") (class "Default")
      (node (ref "JB") (pin "57") (pinfunction "57_57") (pintype "passive+no_connect"))
    )
    (net (code "207") (name "unconnected-(JB-Pad58)") (class "Default")
      (node (ref "JB") (pin "58") (pinfunction "58_58") (pintype "passive+no_connect"))
    )
    (net (code "208") (name "unconnected-(JB-Pad60)") (class "Default")
      (node (ref "JB") (pin "60") (pinfunction "60_60") (pintype "passive+no_connect"))
    )
    (net (code "209") (name "unconnected-(JB-Pad61)") (class "Default")
      (node (ref "JB") (pin "61") (pinfunction "61_61") (pintype "passive+no_connect"))
    )
    (net (code "210") (name "unconnected-(JB-Pad62)") (class "Default")
      (node (ref "JB") (pin "62") (pinfunction "62_62") (pintype "passive+no_connect"))
    )
    (net (code "211") (name "unconnected-(JB-Pad63)") (class "Default")
      (node (ref "JB") (pin "63") (pinfunction "63_63") (pintype "passive+no_connect"))
    )
    (net (code "212") (name "unconnected-(JB-Pad66)") (class "Default")
      (node (ref "JB") (pin "66") (pinfunction "66_66") (pintype "passive+no_connect"))
    )
    (net (code "213") (name "unconnected-(P1-Pad41)") (class "Default")
      (node (ref "P1") (pin "41") (pinfunction "41_41") (pintype "passive"))
    )
    (net (code "214") (name "unconnected-(P1-Pad42)") (class "Default")
      (node (ref "P1") (pin "42") (pinfunction "42_42") (pintype "passive"))
    )
    (net (code "215") (name "unconnected-(P1-Pad43)") (class "Default")
      (node (ref "P1") (pin "43") (pinfunction "43_43") (pintype "passive"))
    )
    (net (code "216") (name "unconnected-(P1-Pad44)") (class "Default")
      (node (ref "P1") (pin "44") (pinfunction "44_44") (pintype "passive"))
    )
    (net (code "217") (name "unconnected-(P1-Pad45)") (class "Default")
      (node (ref "P1") (pin "45") (pinfunction "45_45") (pintype "passive"))
    )
    (net (code "218") (name "unconnected-(P1-Pad46)") (class "Default")
      (node (ref "P1") (pin "46") (pinfunction "46_46") (pintype "passive"))
    )
    (net (code "219") (name "unconnected-(P1-Pad47)") (class "Default")
      (node (ref "P1") (pin "47") (pinfunction "47_47") (pintype "passive"))
    )
    (net (code "220") (name "unconnected-(P1-Pad48)") (class "Default")
      (node (ref "P1") (pin "48") (pinfunction "48_48") (pintype "passive"))
    )
  )
)
